# W101X.net
KiCad netlist of a schematic drawn in EAGLE
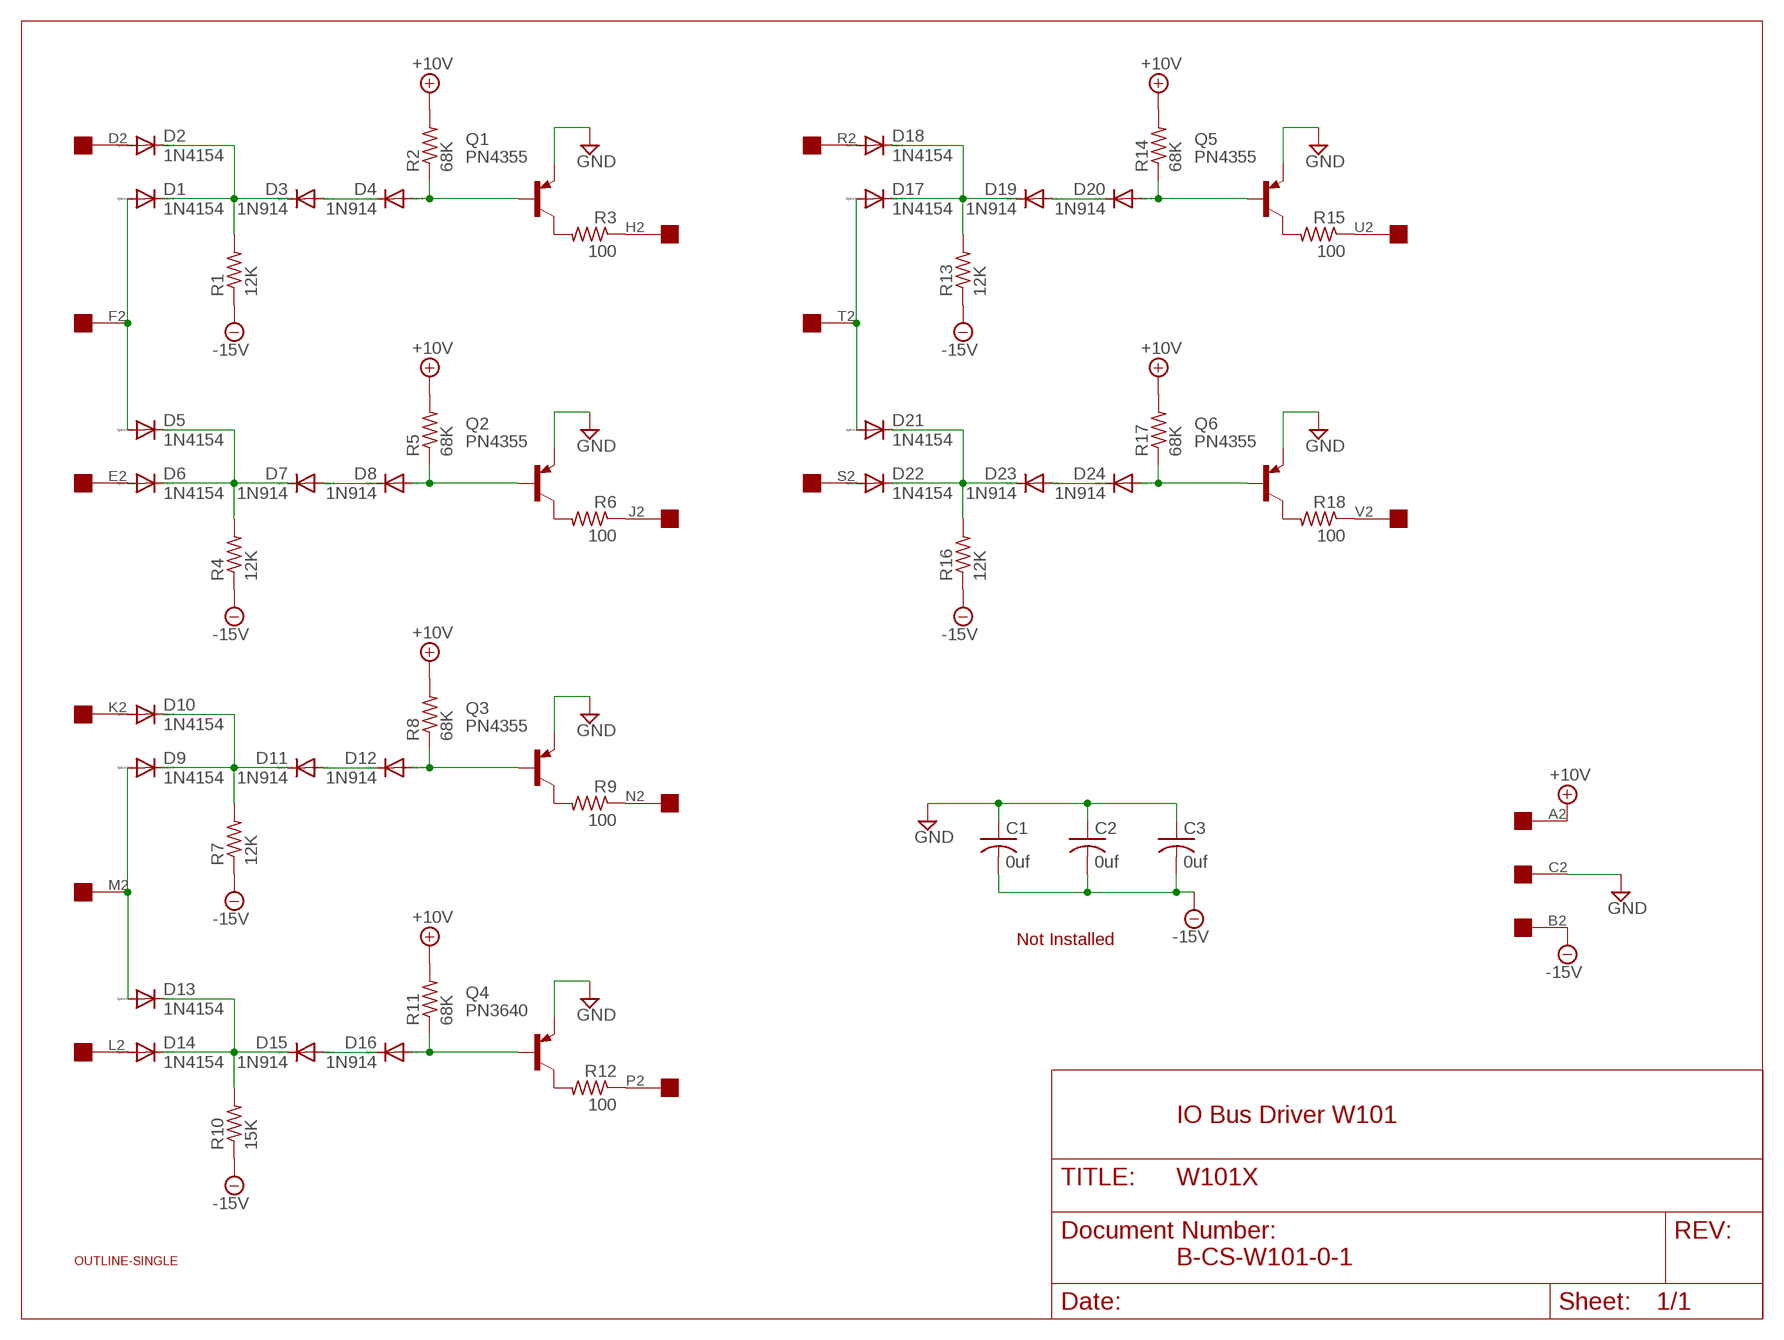
[diagram p0: schematic, sheet 1]

(export (version "E")
  (design (tool "Eeschema 10.0.6"))
  (components
    (comp (ref "C1")
      (value "0uf")
      (footprint "eagle-import:C050-025X075")
      (libsource (lib "eagle-import") (part "C-US050-025X075"))
    )
    (comp (ref "C2")
      (value "0uf")
      (footprint "eagle-import:C050-025X075")
      (libsource (lib "eagle-import") (part "C-US050-025X075"))
    )
    (comp (ref "C3")
      (value "0uf")
      (footprint "eagle-import:C050-025X075")
      (libsource (lib "eagle-import") (part "C-US050-025X075"))
    )
    (comp (ref "D1")
      (value "1N4154")
      (footprint "eagle-import:DO35-10")
      (libsource (lib "eagle-import") (part "1N4148DO35-10"))
    )
    (comp (ref "D2")
      (value "1N4154")
      (footprint "eagle-import:DO35-10")
      (libsource (lib "eagle-import") (part "1N4148DO35-10"))
    )
    (comp (ref "D3")
      (value "1N914")
      (footprint "eagle-import:DO35-10")
      (libsource (lib "eagle-import") (part "1N4148DO35-10"))
    )
    (comp (ref "D4")
      (value "1N914")
      (footprint "eagle-import:DO35-10")
      (libsource (lib "eagle-import") (part "1N4148DO35-10"))
    )
    (comp (ref "D5")
      (value "1N4154")
      (footprint "eagle-import:DO35-10")
      (libsource (lib "eagle-import") (part "1N4148DO35-10"))
    )
    (comp (ref "D6")
      (value "1N4154")
      (footprint "eagle-import:DO35-10")
      (libsource (lib "eagle-import") (part "1N4148DO35-10"))
    )
    (comp (ref "D7")
      (value "1N914")
      (footprint "eagle-import:DO35-10")
      (libsource (lib "eagle-import") (part "1N4148DO35-10"))
    )
    (comp (ref "D8")
      (value "1N914")
      (footprint "eagle-import:DO35-10")
      (libsource (lib "eagle-import") (part "1N4148DO35-10"))
    )
    (comp (ref "D9")
      (value "1N4154")
      (footprint "eagle-import:DO35-10")
      (libsource (lib "eagle-import") (part "1N4148DO35-10"))
    )
    (comp (ref "D10")
      (value "1N4154")
      (footprint "eagle-import:DO35-10")
      (libsource (lib "eagle-import") (part "1N4148DO35-10"))
    )
    (comp (ref "D11")
      (value "1N914")
      (footprint "eagle-import:DO35-10")
      (libsource (lib "eagle-import") (part "1N4148DO35-10"))
    )
    (comp (ref "D12")
      (value "1N914")
      (footprint "eagle-import:DO35-10")
      (libsource (lib "eagle-import") (part "1N4148DO35-10"))
    )
    (comp (ref "D13")
      (value "1N4154")
      (footprint "eagle-import:DO35-10")
      (libsource (lib "eagle-import") (part "1N4148DO35-10"))
    )
    (comp (ref "D14")
      (value "1N4154")
      (footprint "eagle-import:DO35-10")
      (libsource (lib "eagle-import") (part "1N4148DO35-10"))
    )
    (comp (ref "D15")
      (value "1N914")
      (footprint "eagle-import:DO35-10")
      (libsource (lib "eagle-import") (part "1N4148DO35-10"))
    )
    (comp (ref "D16")
      (value "1N914")
      (footprint "eagle-import:DO35-10")
      (libsource (lib "eagle-import") (part "1N4148DO35-10"))
    )
    (comp (ref "D17")
      (value "1N4154")
      (footprint "eagle-import:DO35-10")
      (libsource (lib "eagle-import") (part "1N4148DO35-10"))
    )
    (comp (ref "D18")
      (value "1N4154")
      (footprint "eagle-import:DO35-10")
      (libsource (lib "eagle-import") (part "1N4148DO35-10"))
    )
    (comp (ref "D19")
      (value "1N914")
      (footprint "eagle-import:DO35-10")
      (libsource (lib "eagle-import") (part "1N4148DO35-10"))
    )
    (comp (ref "D20")
      (value "1N914")
      (footprint "eagle-import:DO35-10")
      (libsource (lib "eagle-import") (part "1N4148DO35-10"))
    )
    (comp (ref "D21")
      (value "1N4154")
      (footprint "eagle-import:DO35-10")
      (libsource (lib "eagle-import") (part "1N4148DO35-10"))
    )
    (comp (ref "D22")
      (value "1N4154")
      (footprint "eagle-import:DO35-10")
      (libsource (lib "eagle-import") (part "1N4148DO35-10"))
    )
    (comp (ref "D23")
      (value "1N914")
      (footprint "eagle-import:DO35-10")
      (libsource (lib "eagle-import") (part "1N4148DO35-10"))
    )
    (comp (ref "D24")
      (value "1N914")
      (footprint "eagle-import:DO35-10")
      (libsource (lib "eagle-import") (part "1N4148DO35-10"))
    )
    (comp (ref "Q1")
      (value "PN4355")
      (footprint "eagle-import:TO39")
      (libsource (lib "eagle-import") (part "2N3637"))
    )
    (comp (ref "Q2")
      (value "PN4355")
      (footprint "eagle-import:TO39")
      (libsource (lib "eagle-import") (part "2N3637"))
    )
    (comp (ref "Q3")
      (value "PN4355")
      (footprint "eagle-import:TO39")
      (libsource (lib "eagle-import") (part "2N3637"))
    )
    (comp (ref "Q4")
      (value "PN3640")
      (footprint "eagle-import:TO39")
      (libsource (lib "eagle-import") (part "2N3637"))
    )
    (comp (ref "Q5")
      (value "PN4355")
      (footprint "eagle-import:TO39")
      (libsource (lib "eagle-import") (part "2N3637"))
    )
    (comp (ref "Q6")
      (value "PN4355")
      (footprint "eagle-import:TO39")
      (libsource (lib "eagle-import") (part "2N3637"))
    )
    (comp (ref "R1")
      (value "12K")
      (footprint "eagle-import:0207_10")
      (libsource (lib "eagle-import") (part "R-US_0207/10"))
    )
    (comp (ref "R2")
      (value "68K")
      (footprint "eagle-import:0207_10")
      (libsource (lib "eagle-import") (part "R-US_0207/10"))
    )
    (comp (ref "R3")
      (value "100")
      (footprint "eagle-import:0207_10")
      (libsource (lib "eagle-import") (part "R-US_0207/10"))
    )
    (comp (ref "R4")
      (value "12K")
      (footprint "eagle-import:0207_10")
      (libsource (lib "eagle-import") (part "R-US_0207/10"))
    )
    (comp (ref "R5")
      (value "68K")
      (footprint "eagle-import:0207_10")
      (libsource (lib "eagle-import") (part "R-US_0207/10"))
    )
    (comp (ref "R6")
      (value "100")
      (footprint "eagle-import:0207_10")
      (libsource (lib "eagle-import") (part "R-US_0207/10"))
    )
    (comp (ref "R7")
      (value "12K")
      (footprint "eagle-import:0207_10")
      (libsource (lib "eagle-import") (part "R-US_0207/10"))
    )
    (comp (ref "R8")
      (value "68K")
      (footprint "eagle-import:0207_10")
      (libsource (lib "eagle-import") (part "R-US_0207/10"))
    )
    (comp (ref "R9")
      (value "100")
      (footprint "eagle-import:0207_10")
      (libsource (lib "eagle-import") (part "R-US_0207/10"))
    )
    (comp (ref "R10")
      (value "15K")
      (footprint "eagle-import:0207_10")
      (libsource (lib "eagle-import") (part "R-US_0207/10"))
    )
    (comp (ref "R11")
      (value "68K")
      (footprint "eagle-import:0207_10")
      (libsource (lib "eagle-import") (part "R-US_0207/10"))
    )
    (comp (ref "R12")
      (value "100")
      (footprint "eagle-import:0207_10")
      (libsource (lib "eagle-import") (part "R-US_0207/10"))
    )
    (comp (ref "R13")
      (value "12K")
      (footprint "eagle-import:0207_10")
      (libsource (lib "eagle-import") (part "R-US_0207/10"))
    )
    (comp (ref "R14")
      (value "68K")
      (footprint "eagle-import:0207_10")
      (libsource (lib "eagle-import") (part "R-US_0207/10"))
    )
    (comp (ref "R15")
      (value "100")
      (footprint "eagle-import:0207_10")
      (libsource (lib "eagle-import") (part "R-US_0207/10"))
    )
    (comp (ref "R16")
      (value "12K")
      (footprint "eagle-import:0207_10")
      (libsource (lib "eagle-import") (part "R-US_0207/10"))
    )
    (comp (ref "R17")
      (value "68K")
      (footprint "eagle-import:0207_10")
      (libsource (lib "eagle-import") (part "R-US_0207/10"))
    )
    (comp (ref "R18")
      (value "100")
      (footprint "eagle-import:0207_10")
      (libsource (lib "eagle-import") (part "R-US_0207/10"))
    )
    (comp (ref "U$1")
      (value "OUTLINE-SINGLE")
      (footprint "eagle-import:SINGLE")
      (libsource (lib "eagle-import") (part "OUTLINE-SINGLE"))
    )
    (comp (ref "U$2")
      (value "EDGE-1")
      (footprint "eagle-import:EDGE-CON1")
      (libsource (lib "eagle-import") (part "EDGE-1"))
    )
  )
  (nets
    (net (code "1") (name "+10V") (class "Default")
      (node (ref "R11") (pin "2") (pinfunction "2_2") (pintype "passive"))
      (node (ref "R14") (pin "2") (pinfunction "2_2") (pintype "passive"))
      (node (ref "R17") (pin "2") (pinfunction "2_2") (pintype "passive"))
      (node (ref "R2") (pin "2") (pinfunction "2_2") (pintype "passive"))
      (node (ref "R5") (pin "2") (pinfunction "2_2") (pintype "passive"))
      (node (ref "R8") (pin "2") (pinfunction "2_2") (pintype "passive"))
      (node (ref "U$2") (pin "A2") (pinfunction "1_A2") (pintype "bidirectional"))
    )
    (net (code "2") (name "-15V") (class "Default")
      (node (ref "C1") (pin "2") (pinfunction "2_2") (pintype "passive"))
      (node (ref "C2") (pin "2") (pinfunction "2_2") (pintype "passive"))
      (node (ref "C3") (pin "2") (pinfunction "2_2") (pintype "passive"))
      (node (ref "R1") (pin "1") (pinfunction "1_1") (pintype "passive"))
      (node (ref "R10") (pin "1") (pinfunction "1_1") (pintype "passive"))
      (node (ref "R13") (pin "1") (pinfunction "1_1") (pintype "passive"))
      (node (ref "R16") (pin "1") (pinfunction "1_1") (pintype "passive"))
      (node (ref "R4") (pin "1") (pinfunction "1_1") (pintype "passive"))
      (node (ref "R7") (pin "1") (pinfunction "1_1") (pintype "passive"))
      (node (ref "U$2") (pin "B2") (pinfunction "1_B2") (pintype "bidirectional"))
    )
    (net (code "3") (name "GND") (class "Default")
      (node (ref "C1") (pin "1") (pinfunction "1_1") (pintype "passive"))
      (node (ref "C2") (pin "1") (pinfunction "1_1") (pintype "passive"))
      (node (ref "C3") (pin "1") (pinfunction "1_1") (pintype "passive"))
      (node (ref "Q1") (pin "1") (pinfunction "E_1") (pintype "passive"))
      (node (ref "Q2") (pin "1") (pinfunction "E_1") (pintype "passive"))
      (node (ref "Q3") (pin "1") (pinfunction "E_1") (pintype "passive"))
      (node (ref "Q4") (pin "1") (pinfunction "E_1") (pintype "passive"))
      (node (ref "Q5") (pin "1") (pinfunction "E_1") (pintype "passive"))
      (node (ref "Q6") (pin "1") (pinfunction "E_1") (pintype "passive"))
      (node (ref "U$2") (pin "C2") (pinfunction "1_C2") (pintype "bidirectional"))
    )
    (net (code "4") (name "Net-(D1-PadC)") (class "Default")
      (node (ref "D1") (pin "C") (pinfunction "C_C") (pintype "passive"))
      (node (ref "D2") (pin "C") (pinfunction "C_C") (pintype "passive"))
      (node (ref "D3") (pin "C") (pinfunction "C_C") (pintype "passive"))
      (node (ref "R1") (pin "2") (pinfunction "2_2") (pintype "passive"))
    )
    (net (code "5") (name "Net-(D3-PadA)") (class "Default")
      (node (ref "D3") (pin "A") (pinfunction "A_A") (pintype "passive"))
      (node (ref "D4") (pin "C") (pinfunction "C_C") (pintype "passive"))
    )
    (net (code "6") (name "Net-(D5-PadC)") (class "Default")
      (node (ref "D5") (pin "C") (pinfunction "C_C") (pintype "passive"))
      (node (ref "D6") (pin "C") (pinfunction "C_C") (pintype "passive"))
      (node (ref "D7") (pin "C") (pinfunction "C_C") (pintype "passive"))
      (node (ref "R4") (pin "2") (pinfunction "2_2") (pintype "passive"))
    )
    (net (code "7") (name "Net-(D7-PadA)") (class "Default")
      (node (ref "D7") (pin "A") (pinfunction "A_A") (pintype "passive"))
      (node (ref "D8") (pin "C") (pinfunction "C_C") (pintype "passive"))
    )
    (net (code "8") (name "Net-(D10-PadC)") (class "Default")
      (node (ref "D10") (pin "C") (pinfunction "C_C") (pintype "passive"))
      (node (ref "D11") (pin "C") (pinfunction "C_C") (pintype "passive"))
      (node (ref "D9") (pin "C") (pinfunction "C_C") (pintype "passive"))
      (node (ref "R7") (pin "2") (pinfunction "2_2") (pintype "passive"))
    )
    (net (code "9") (name "Net-(D11-PadA)") (class "Default")
      (node (ref "D11") (pin "A") (pinfunction "A_A") (pintype "passive"))
      (node (ref "D12") (pin "C") (pinfunction "C_C") (pintype "passive"))
    )
    (net (code "10") (name "Net-(D13-PadC)") (class "Default")
      (node (ref "D13") (pin "C") (pinfunction "C_C") (pintype "passive"))
      (node (ref "D14") (pin "C") (pinfunction "C_C") (pintype "passive"))
      (node (ref "D15") (pin "C") (pinfunction "C_C") (pintype "passive"))
      (node (ref "R10") (pin "2") (pinfunction "2_2") (pintype "passive"))
    )
    (net (code "11") (name "Net-(D15-PadA)") (class "Default")
      (node (ref "D15") (pin "A") (pinfunction "A_A") (pintype "passive"))
      (node (ref "D16") (pin "C") (pinfunction "C_C") (pintype "passive"))
    )
    (net (code "12") (name "Net-(D17-PadC)") (class "Default")
      (node (ref "D17") (pin "C") (pinfunction "C_C") (pintype "passive"))
      (node (ref "D18") (pin "C") (pinfunction "C_C") (pintype "passive"))
      (node (ref "D19") (pin "C") (pinfunction "C_C") (pintype "passive"))
      (node (ref "R13") (pin "2") (pinfunction "2_2") (pintype "passive"))
    )
    (net (code "13") (name "Net-(D19-PadA)") (class "Default")
      (node (ref "D19") (pin "A") (pinfunction "A_A") (pintype "passive"))
      (node (ref "D20") (pin "C") (pinfunction "C_C") (pintype "passive"))
    )
    (net (code "14") (name "Net-(D21-PadC)") (class "Default")
      (node (ref "D21") (pin "C") (pinfunction "C_C") (pintype "passive"))
      (node (ref "D22") (pin "C") (pinfunction "C_C") (pintype "passive"))
      (node (ref "D23") (pin "C") (pinfunction "C_C") (pintype "passive"))
      (node (ref "R16") (pin "2") (pinfunction "2_2") (pintype "passive"))
    )
    (net (code "15") (name "Net-(D23-PadA)") (class "Default")
      (node (ref "D23") (pin "A") (pinfunction "A_A") (pintype "passive"))
      (node (ref "D24") (pin "C") (pinfunction "C_C") (pintype "passive"))
    )
    (net (code "16") (name "Net-(Q1-B)") (class "Default")
      (node (ref "D4") (pin "A") (pinfunction "A_A") (pintype "passive"))
      (node (ref "Q1") (pin "2") (pinfunction "B_2") (pintype "passive"))
      (node (ref "R2") (pin "1") (pinfunction "1_1") (pintype "passive"))
    )
    (net (code "17") (name "Net-(Q1-C)") (class "Default")
      (node (ref "Q1") (pin "3") (pinfunction "C_3") (pintype "passive"))
      (node (ref "R3") (pin "2") (pinfunction "2_2") (pintype "passive"))
    )
    (net (code "18") (name "Net-(Q2-B)") (class "Default")
      (node (ref "D8") (pin "A") (pinfunction "A_A") (pintype "passive"))
      (node (ref "Q2") (pin "2") (pinfunction "B_2") (pintype "passive"))
      (node (ref "R5") (pin "1") (pinfunction "1_1") (pintype "passive"))
    )
    (net (code "19") (name "Net-(Q2-C)") (class "Default")
      (node (ref "Q2") (pin "3") (pinfunction "C_3") (pintype "passive"))
      (node (ref "R6") (pin "2") (pinfunction "2_2") (pintype "passive"))
    )
    (net (code "20") (name "Net-(Q3-B)") (class "Default")
      (node (ref "D12") (pin "A") (pinfunction "A_A") (pintype "passive"))
      (node (ref "Q3") (pin "2") (pinfunction "B_2") (pintype "passive"))
      (node (ref "R8") (pin "1") (pinfunction "1_1") (pintype "passive"))
    )
    (net (code "21") (name "Net-(Q3-C)") (class "Default")
      (node (ref "Q3") (pin "3") (pinfunction "C_3") (pintype "passive"))
      (node (ref "R9") (pin "2") (pinfunction "2_2") (pintype "passive"))
    )
    (net (code "22") (name "Net-(Q4-B)") (class "Default")
      (node (ref "D16") (pin "A") (pinfunction "A_A") (pintype "passive"))
      (node (ref "Q4") (pin "2") (pinfunction "B_2") (pintype "passive"))
      (node (ref "R11") (pin "1") (pinfunction "1_1") (pintype "passive"))
    )
    (net (code "23") (name "Net-(Q4-C)") (class "Default")
      (node (ref "Q4") (pin "3") (pinfunction "C_3") (pintype "passive"))
      (node (ref "R12") (pin "2") (pinfunction "2_2") (pintype "passive"))
    )
    (net (code "24") (name "Net-(Q5-B)") (class "Default")
      (node (ref "D20") (pin "A") (pinfunction "A_A") (pintype "passive"))
      (node (ref "Q5") (pin "2") (pinfunction "B_2") (pintype "passive"))
      (node (ref "R14") (pin "1") (pinfunction "1_1") (pintype "passive"))
    )
    (net (code "25") (name "Net-(Q5-C)") (class "Default")
      (node (ref "Q5") (pin "3") (pinfunction "C_3") (pintype "passive"))
      (node (ref "R15") (pin "2") (pinfunction "2_2") (pintype "passive"))
    )
    (net (code "26") (name "Net-(Q6-B)") (class "Default")
      (node (ref "D24") (pin "A") (pinfunction "A_A") (pintype "passive"))
      (node (ref "Q6") (pin "2") (pinfunction "B_2") (pintype "passive"))
      (node (ref "R17") (pin "1") (pinfunction "1_1") (pintype "passive"))
    )
    (net (code "27") (name "Net-(Q6-C)") (class "Default")
      (node (ref "Q6") (pin "3") (pinfunction "C_3") (pintype "passive"))
      (node (ref "R18") (pin "2") (pinfunction "2_2") (pintype "passive"))
    )
    (net (code "28") (name "Net-(U$2D-1)") (class "Default")
      (node (ref "D2") (pin "A") (pinfunction "A_A") (pintype "passive"))
      (node (ref "U$2") (pin "D2") (pinfunction "1_D2") (pintype "bidirectional"))
    )
    (net (code "29") (name "Net-(U$2E-1)") (class "Default")
      (node (ref "D6") (pin "A") (pinfunction "A_A") (pintype "passive"))
      (node (ref "U$2") (pin "E2") (pinfunction "1_E2") (pintype "bidirectional"))
    )
    (net (code "30") (name "Net-(U$2F-1)") (class "Default")
      (node (ref "D1") (pin "A") (pinfunction "A_A") (pintype "passive"))
      (node (ref "D5") (pin "A") (pinfunction "A_A") (pintype "passive"))
      (node (ref "U$2") (pin "F2") (pinfunction "1_F2") (pintype "bidirectional"))
    )
    (net (code "31") (name "Net-(U$2G-1)") (class "Default")
      (node (ref "R3") (pin "1") (pinfunction "1_1") (pintype "passive"))
      (node (ref "U$2") (pin "H2") (pinfunction "1_H2") (pintype "bidirectional"))
    )
    (net (code "32") (name "Net-(U$2H-1)") (class "Default")
      (node (ref "R6") (pin "1") (pinfunction "1_1") (pintype "passive"))
      (node (ref "U$2") (pin "J2") (pinfunction "1_J2") (pintype "bidirectional"))
    )
    (net (code "33") (name "Net-(U$2I-1)") (class "Default")
      (node (ref "D10") (pin "A") (pinfunction "A_A") (pintype "passive"))
      (node (ref "U$2") (pin "K2") (pinfunction "1_K2") (pintype "bidirectional"))
    )
    (net (code "34") (name "Net-(U$2J-1)") (class "Default")
      (node (ref "D14") (pin "A") (pinfunction "A_A") (pintype "passive"))
      (node (ref "U$2") (pin "L2") (pinfunction "1_L2") (pintype "bidirectional"))
    )
    (net (code "35") (name "Net-(U$2K-1)") (class "Default")
      (node (ref "D13") (pin "A") (pinfunction "A_A") (pintype "passive"))
      (node (ref "D9") (pin "A") (pinfunction "A_A") (pintype "passive"))
      (node (ref "U$2") (pin "M2") (pinfunction "1_M2") (pintype "bidirectional"))
    )
    (net (code "36") (name "Net-(U$2L-1)") (class "Default")
      (node (ref "R9") (pin "1") (pinfunction "1_1") (pintype "passive"))
      (node (ref "U$2") (pin "N2") (pinfunction "1_N2") (pintype "bidirectional"))
    )
    (net (code "37") (name "Net-(U$2M-1)") (class "Default")
      (node (ref "R12") (pin "1") (pinfunction "1_1") (pintype "passive"))
      (node (ref "U$2") (pin "P2") (pinfunction "1_P2") (pintype "bidirectional"))
    )
    (net (code "38") (name "Net-(U$2N-1)") (class "Default")
      (node (ref "D18") (pin "A") (pinfunction "A_A") (pintype "passive"))
      (node (ref "U$2") (pin "R2") (pinfunction "1_R2") (pintype "bidirectional"))
    )
    (net (code "39") (name "Net-(U$2O-1)") (class "Default")
      (node (ref "D22") (pin "A") (pinfunction "A_A") (pintype "passive"))
      (node (ref "U$2") (pin "S2") (pinfunction "1_S2") (pintype "bidirectional"))
    )
    (net (code "40") (name "Net-(U$2P-1)") (class "Default")
      (node (ref "D17") (pin "A") (pinfunction "A_A") (pintype "passive"))
      (node (ref "D21") (pin "A") (pinfunction "A_A") (pintype "passive"))
      (node (ref "U$2") (pin "T2") (pinfunction "1_T2") (pintype "bidirectional"))
    )
    (net (code "41") (name "Net-(U$2Q-1)") (class "Default")
      (node (ref "R15") (pin "1") (pinfunction "1_1") (pintype "passive"))
      (node (ref "U$2") (pin "U2") (pinfunction "1_U2") (pintype "bidirectional"))
    )
    (net (code "42") (name "Net-(U$2R-1)") (class "Default")
      (node (ref "R18") (pin "1") (pinfunction "1_1") (pintype "passive"))
      (node (ref "U$2") (pin "V2") (pinfunction "1_V2") (pintype "bidirectional"))
    )
  )
)
